# PogoPinSide.net
KiCad netlist of a schematic drawn in Altium Designer
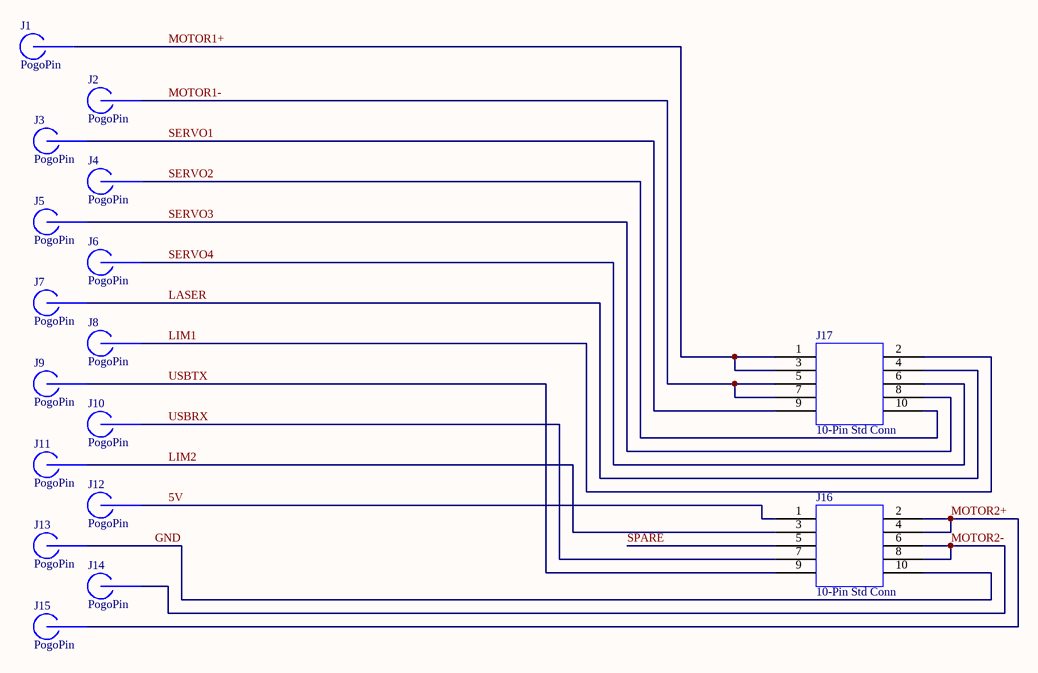
[diagram p0: PogoPinSide.SchDoc]

(export (version "E")
  (design (tool "Eeschema 10.0.6"))
  (components
    (comp (ref "J1")
      (value "PogoPin")
      (footprint "PCBComponent_1")
      (libsource (lib "Husky Robotics Standard Library 2019-2020") (part "PogoPin"))
    )
    (comp (ref "J2")
      (value "PogoPin")
      (footprint "PCBComponent_1")
      (libsource (lib "Husky Robotics Standard Library 2019-2020") (part "PogoPin"))
    )
    (comp (ref "J3")
      (value "PogoPin")
      (footprint "PCBComponent_1")
      (libsource (lib "Husky Robotics Standard Library 2019-2020") (part "PogoPin"))
    )
    (comp (ref "J4") (value "PogoPin") (footprint "PCBComponent_1") (libsource (lib "") (part "PogoPin_1")))
    (comp (ref "J5")
      (value "PogoPin")
      (footprint "PCBComponent_1")
      (libsource (lib "Husky Robotics Standard Library 2019-2020") (part "PogoPin"))
    )
    (comp (ref "J6")
      (value "PogoPin")
      (footprint "PCBComponent_1")
      (libsource (lib "Husky Robotics Standard Library 2019-2020") (part "PogoPin"))
    )
    (comp (ref "J7")
      (value "PogoPin")
      (footprint "PCBComponent_1")
      (libsource (lib "Husky Robotics Standard Library 2019-2020") (part "PogoPin"))
    )
    (comp (ref "J8")
      (value "PogoPin")
      (footprint "PCBComponent_1")
      (libsource (lib "Husky Robotics Standard Library 2019-2020") (part "PogoPin"))
    )
    (comp (ref "J9")
      (value "PogoPin")
      (footprint "PCBComponent_1")
      (libsource (lib "Husky Robotics Standard Library 2019-2020") (part "PogoPin"))
    )
    (comp (ref "J10")
      (value "PogoPin")
      (footprint "PCBComponent_1")
      (libsource (lib "Husky Robotics Standard Library 2019-2020") (part "PogoPin"))
    )
    (comp (ref "J11")
      (value "PogoPin")
      (footprint "PCBComponent_1")
      (libsource (lib "Husky Robotics Standard Library 2019-2020") (part "PogoPin"))
    )
    (comp (ref "J12")
      (value "PogoPin")
      (footprint "PCBComponent_1")
      (libsource (lib "Husky Robotics Standard Library 2019-2020") (part "PogoPin"))
    )
    (comp (ref "J13")
      (value "PogoPin")
      (footprint "PCBComponent_1")
      (libsource (lib "Husky Robotics Standard Library 2019-2020") (part "PogoPin"))
    )
    (comp (ref "J14")
      (value "PogoPin")
      (footprint "PCBComponent_1")
      (libsource (lib "Husky Robotics Standard Library 2019-2020") (part "PogoPin"))
    )
    (comp (ref "J15")
      (value "PogoPin")
      (footprint "PCBComponent_1")
      (libsource (lib "Husky Robotics Standard Library 2019-2020") (part "PogoPin"))
    )
    (comp (ref "J16")
      (value "10-Pin Std Conn")
      (footprint "FTSH-105-01-F-DV")
      (libsource (lib "Husky Robotics Standard Library 2019-2020") (part "10-Pin Std Conn"))
    )
    (comp (ref "J17")
      (value "10-Pin Std Conn")
      (footprint "FTSH-105-01-F-DV")
      (libsource (lib "Husky Robotics Standard Library 2019-2020") (part "10-Pin Std Conn"))
    )
  )
  (nets
    (net (code "1") (name "/5V") (class "Default")
      (node (ref "J12") (pin "1") (pinfunction "Pin_1") (pintype "passive"))
      (node (ref "J16") (pin "1") (pinfunction "Pin_1") (pintype "passive"))
    )
    (net (code "2") (name "/GND") (class "Default")
      (node (ref "J13") (pin "1") (pinfunction "Pin_1") (pintype "passive"))
      (node (ref "J16") (pin "10") (pinfunction "Pin_10") (pintype "passive"))
    )
    (net (code "3") (name "/LASER") (class "Default")
      (node (ref "J17") (pin "4") (pinfunction "Pin_4") (pintype "passive"))
      (node (ref "J7") (pin "1") (pinfunction "Pin_1") (pintype "passive"))
    )
    (net (code "4") (name "/LIM1") (class "Default")
      (node (ref "J17") (pin "2") (pinfunction "Pin_2") (pintype "passive"))
      (node (ref "J8") (pin "1") (pinfunction "Pin_1") (pintype "passive"))
    )
    (net (code "5") (name "/LIM2") (class "Default")
      (node (ref "J11") (pin "1") (pinfunction "Pin_1") (pintype "passive"))
      (node (ref "J16") (pin "3") (pinfunction "Pin_3") (pintype "passive"))
    )
    (net (code "6") (name "/MOTOR1+") (class "Default")
      (node (ref "J1") (pin "1") (pinfunction "Pin_1") (pintype "passive"))
      (node (ref "J17") (pin "1") (pinfunction "Pin_1") (pintype "passive"))
      (node (ref "J17") (pin "3") (pinfunction "Pin_3") (pintype "passive"))
    )
    (net (code "7") (name "/MOTOR1-") (class "Default")
      (node (ref "J17") (pin "5") (pinfunction "Pin_5") (pintype "passive"))
      (node (ref "J17") (pin "7") (pinfunction "Pin_7") (pintype "passive"))
      (node (ref "J2") (pin "1") (pinfunction "Pin_1") (pintype "passive"))
    )
    (net (code "8") (name "/MOTOR2+") (class "Default")
      (node (ref "J15") (pin "1") (pinfunction "Pin_1") (pintype "passive"))
      (node (ref "J16") (pin "2") (pinfunction "Pin_2") (pintype "passive"))
      (node (ref "J16") (pin "4") (pinfunction "Pin_4") (pintype "passive"))
    )
    (net (code "9") (name "/MOTOR2-") (class "Default")
      (node (ref "J14") (pin "1") (pinfunction "Pin_1") (pintype "passive"))
      (node (ref "J16") (pin "6") (pinfunction "Pin_6") (pintype "passive"))
      (node (ref "J16") (pin "8") (pinfunction "Pin_8") (pintype "passive"))
    )
    (net (code "10") (name "/SERVO1") (class "Default")
      (node (ref "J17") (pin "9") (pinfunction "Pin_9") (pintype "passive"))
      (node (ref "J3") (pin "1") (pinfunction "Pin_1") (pintype "passive"))
    )
    (net (code "11") (name "/SERVO2") (class "Default")
      (node (ref "J17") (pin "10") (pinfunction "Pin_10") (pintype "passive"))
      (node (ref "J4") (pin "J4") (pinfunction "Pin_J4") (pintype "passive"))
    )
    (net (code "12") (name "/SERVO3") (class "Default")
      (node (ref "J17") (pin "8") (pinfunction "Pin_8") (pintype "passive"))
      (node (ref "J5") (pin "1") (pinfunction "Pin_1") (pintype "passive"))
    )
    (net (code "13") (name "/SERVO4") (class "Default")
      (node (ref "J17") (pin "6") (pinfunction "Pin_6") (pintype "passive"))
      (node (ref "J6") (pin "1") (pinfunction "Pin_1") (pintype "passive"))
    )
    (net (code "14") (name "/SPARE") (class "Default")
      (node (ref "J16") (pin "5") (pinfunction "Pin_5") (pintype "passive"))
    )
    (net (code "15") (name "/USBRX") (class "Default")
      (node (ref "J10") (pin "1") (pinfunction "Pin_1") (pintype "passive"))
      (node (ref "J16") (pin "7") (pinfunction "Pin_7") (pintype "passive"))
    )
    (net (code "16") (name "/USBTX") (class "Default")
      (node (ref "J16") (pin "9") (pinfunction "Pin_9") (pintype "passive"))
      (node (ref "J9") (pin "1") (pinfunction "Pin_1") (pintype "passive"))
    )
  )
)
